# SODIMM.net
KiCad netlist of a schematic drawn in Altium Designer
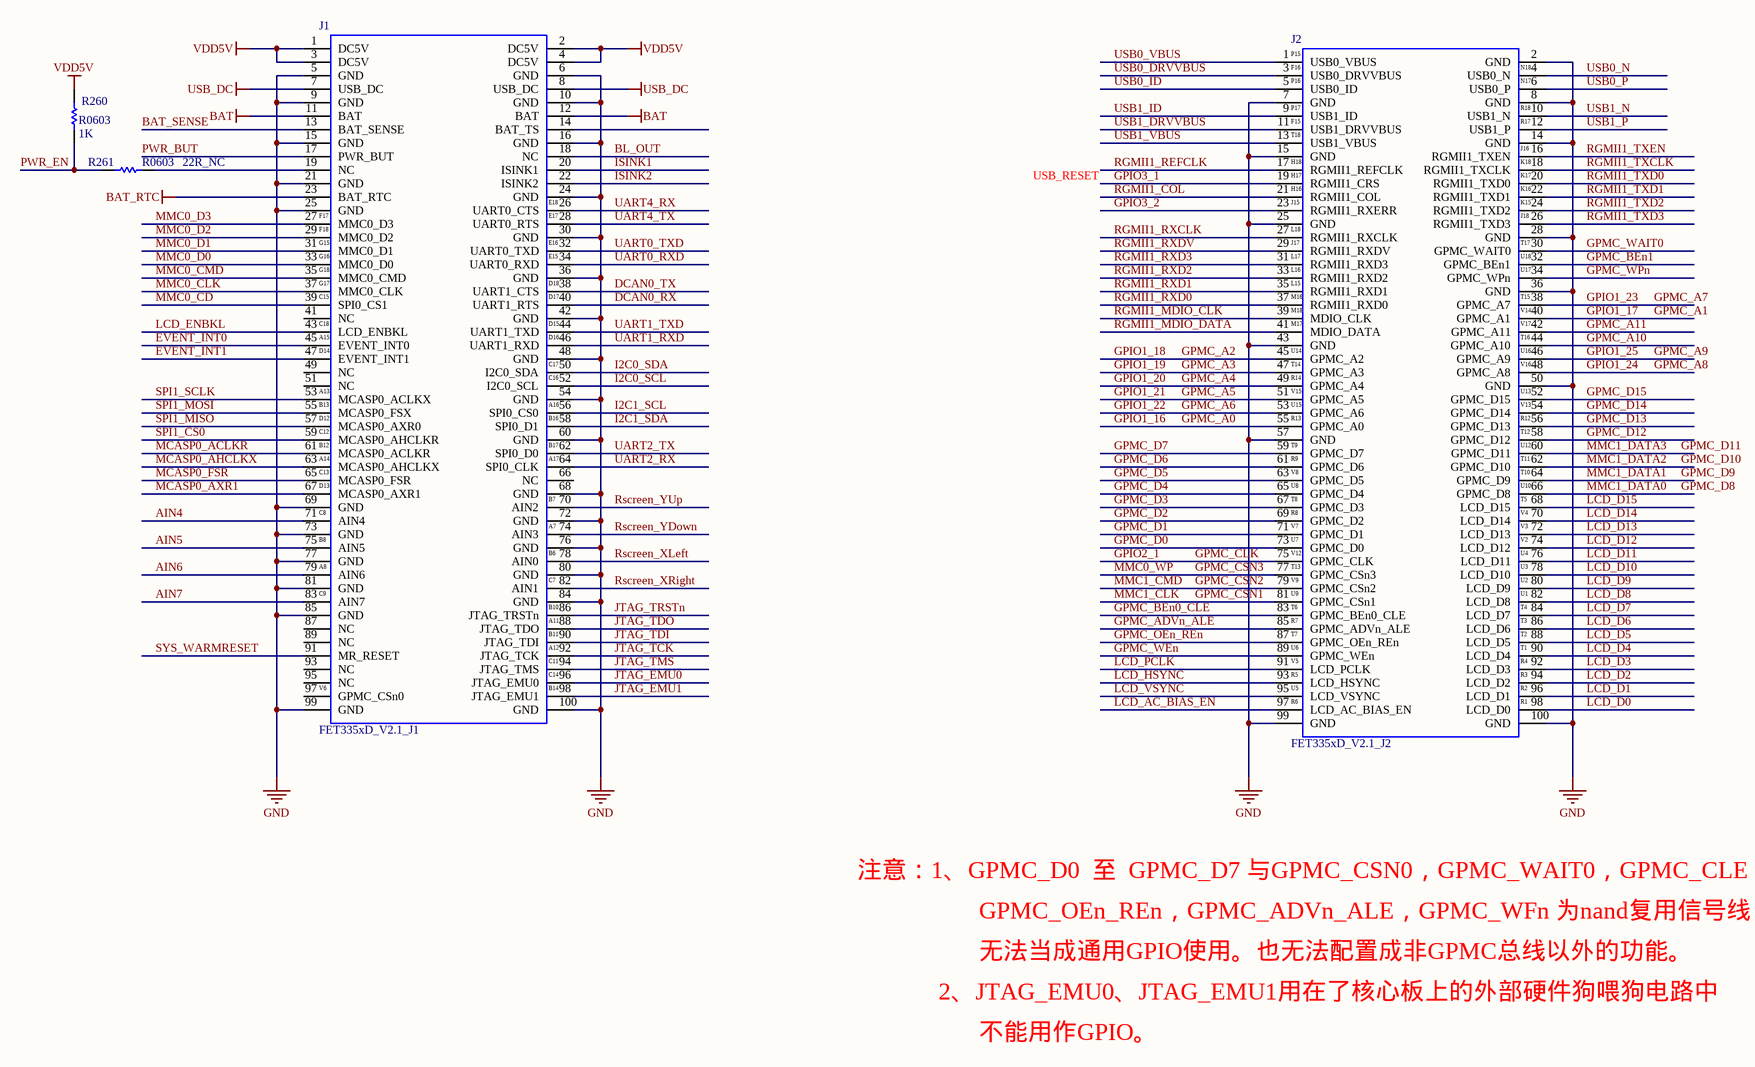
[diagram p0: SODIMM.SchDoc]

(export (version "E")
  (design (tool "Eeschema 10.0.6"))
  (components
    (comp (ref "J1")
      (value "FET335xD_V2.1_J1")
      (footprint "1.27MM SMT CONNECT PIN")
      (libsource (lib "OK335xD") (part "FET335xD_V2.1_J1"))
    )
    (comp (ref "J2")
      (value "FET335xD_V2.1_J2")
      (footprint "1.27MM SMT CONNECT PIN")
      (libsource (lib "OK335xD") (part "FET335xD_V2.1_J2"))
    )
    (comp (ref "R260")
      (value "R0603")
      (footprint "OK335xD_V1.0:R0603_M1608")
      (description "Resistor")
      (fields (field (name "ALTIUM_VALUE") "1K") (field (name "PUBLISHER") "Altium Limited"))
      (libsource (lib "Miscellaneous Devices") (part "Res1"))
    )
    (comp (ref "R261")
      (value "R0603")
      (footprint "OK335xD_V1.0:R0603_M1608")
      (description "Resistor")
      (fields (field (name "ALTIUM_VALUE") "22R_NC") (field (name "PUBLISHER") "Altium Limited"))
      (libsource (lib "Miscellaneous Devices") (part "Res1"))
    )
  )
  (nets
    (net (code "1") (name "/AIN4") (class "Default")
      (node (ref "J1") (pin "71") (pinfunction "AIN4_71") (pintype "passive"))
    )
    (net (code "2") (name "/AIN5") (class "Default")
      (node (ref "J1") (pin "75") (pinfunction "AIN5_75") (pintype "passive"))
    )
    (net (code "3") (name "/AIN6") (class "Default")
      (node (ref "J1") (pin "79") (pinfunction "AIN6_79") (pintype "passive"))
    )
    (net (code "4") (name "/AIN7") (class "Default")
      (node (ref "J1") (pin "83") (pinfunction "AIN7_83") (pintype "passive"))
    )
    (net (code "5") (name "/BAT_SENSE") (class "Default")
      (node (ref "J1") (pin "13") (pinfunction "BAT_SENSE_13") (pintype "passive"))
    )
    (net (code "6") (name "/BL_OUT") (class "Default")
      (node (ref "J1") (pin "18") (pinfunction "NC_18") (pintype "passive"))
    )
    (net (code "7") (name "/DCAN0_RX") (class "Default")
      (node (ref "J1") (pin "40") (pinfunction "UART1_RTS_40") (pintype "passive"))
    )
    (net (code "8") (name "/DCAN0_TX") (class "Default")
      (node (ref "J1") (pin "38") (pinfunction "UART1_CTS_38") (pintype "passive"))
    )
    (net (code "9") (name "/EVENT_INT0") (class "Default")
      (node (ref "J1") (pin "45") (pinfunction "EVENT_INT0_45") (pintype "passive"))
    )
    (net (code "10") (name "/EVENT_INT1") (class "Default")
      (node (ref "J1") (pin "47") (pinfunction "EVENT_INT1_47") (pintype "passive"))
    )
    (net (code "11") (name "/GPIO1_16") (class "Default")
      (node (ref "J2") (pin "55") (pinfunction "GPMC_A0_55") (pintype "passive"))
    )
    (net (code "12") (name "/GPIO1_17") (class "Default")
      (node (ref "J2") (pin "40") (pinfunction "GPMC_A1_40") (pintype "passive"))
    )
    (net (code "13") (name "/GPIO1_18") (class "Default")
      (node (ref "J2") (pin "45") (pinfunction "GPMC_A2_45") (pintype "passive"))
    )
    (net (code "14") (name "/GPIO1_19") (class "Default")
      (node (ref "J2") (pin "47") (pinfunction "GPMC_A3_47") (pintype "passive"))
    )
    (net (code "15") (name "/GPIO1_20") (class "Default")
      (node (ref "J2") (pin "49") (pinfunction "GPMC_A4_49") (pintype "passive"))
    )
    (net (code "16") (name "/GPIO1_21") (class "Default")
      (node (ref "J2") (pin "51") (pinfunction "GPMC_A5_51") (pintype "passive"))
    )
    (net (code "17") (name "/GPIO1_22") (class "Default")
      (node (ref "J2") (pin "53") (pinfunction "GPMC_A6_53") (pintype "passive"))
    )
    (net (code "18") (name "/GPIO1_23") (class "Default")
      (node (ref "J2") (pin "38") (pinfunction "GPMC_A7_38") (pintype "passive"))
    )
    (net (code "19") (name "/GPIO1_24") (class "Default")
      (node (ref "J2") (pin "48") (pinfunction "GPMC_A8_48") (pintype "passive"))
    )
    (net (code "20") (name "/GPIO1_25") (class "Default")
      (node (ref "J2") (pin "46") (pinfunction "GPMC_A9_46") (pintype "passive"))
    )
    (net (code "21") (name "/GPIO2_1") (class "Default")
      (node (ref "J2") (pin "75") (pinfunction "GPMC_CLK_75") (pintype "passive"))
    )
    (net (code "22") (name "/GPIO3_1") (class "Default")
      (node (ref "J2") (pin "19") (pinfunction "RGMII1_CRS_19") (pintype "passive"))
    )
    (net (code "23") (name "/GPIO3_2") (class "Default")
      (node (ref "J2") (pin "23") (pinfunction "RGMII1_RXERR_23") (pintype "passive"))
    )
    (net (code "24") (name "/GPMC_A10") (class "Default")
      (node (ref "J2") (pin "44") (pinfunction "GPMC_A10_44") (pintype "passive"))
    )
    (net (code "25") (name "/GPMC_A11") (class "Default")
      (node (ref "J2") (pin "42") (pinfunction "GPMC_A11_42") (pintype "passive"))
    )
    (net (code "26") (name "/GPMC_ADVn_ALE") (class "Default")
      (node (ref "J2") (pin "85") (pinfunction "GPMC_ADVn_ALE_85") (pintype "passive"))
    )
    (net (code "27") (name "/GPMC_BEn0_CLE") (class "Default")
      (node (ref "J2") (pin "83") (pinfunction "GPMC_BEn0_CLE_83") (pintype "passive"))
    )
    (net (code "28") (name "/GPMC_BEn1") (class "Default")
      (node (ref "J2") (pin "32") (pinfunction "GPMC_BEn1_32") (pintype "passive"))
    )
    (net (code "29") (name "/GPMC_CSN1") (class "Default")
      (node (ref "J2") (pin "81") (pinfunction "GPMC_CSn1_81") (pintype "passive"))
    )
    (net (code "30") (name "/GPMC_CSN2") (class "Default")
      (node (ref "J2") (pin "79") (pinfunction "GPMC_CSn2_79") (pintype "passive"))
    )
    (net (code "31") (name "/GPMC_CSN3") (class "Default")
      (node (ref "J2") (pin "77") (pinfunction "GPMC_CSn3_77") (pintype "passive"))
    )
    (net (code "32") (name "/GPMC_D0") (class "Default")
      (node (ref "J2") (pin "73") (pinfunction "GPMC_D0_73") (pintype "passive"))
    )
    (net (code "33") (name "/GPMC_D1") (class "Default")
      (node (ref "J2") (pin "71") (pinfunction "GPMC_D1_71") (pintype "passive"))
    )
    (net (code "34") (name "/GPMC_D2") (class "Default")
      (node (ref "J2") (pin "69") (pinfunction "GPMC_D2_69") (pintype "passive"))
    )
    (net (code "35") (name "/GPMC_D3") (class "Default")
      (node (ref "J2") (pin "67") (pinfunction "GPMC_D3_67") (pintype "passive"))
    )
    (net (code "36") (name "/GPMC_D4") (class "Default")
      (node (ref "J2") (pin "65") (pinfunction "GPMC_D4_65") (pintype "passive"))
    )
    (net (code "37") (name "/GPMC_D5") (class "Default")
      (node (ref "J2") (pin "63") (pinfunction "GPMC_D5_63") (pintype "passive"))
    )
    (net (code "38") (name "/GPMC_D6") (class "Default")
      (node (ref "J2") (pin "61") (pinfunction "GPMC_D6_61") (pintype "passive"))
    )
    (net (code "39") (name "/GPMC_D7") (class "Default")
      (node (ref "J2") (pin "59") (pinfunction "GPMC_D7_59") (pintype "passive"))
    )
    (net (code "40") (name "/GPMC_D8") (class "Default")
      (node (ref "J2") (pin "66") (pinfunction "GPMC_D8_66") (pintype "passive"))
    )
    (net (code "41") (name "/GPMC_D9") (class "Default")
      (node (ref "J2") (pin "64") (pinfunction "GPMC_D9_64") (pintype "passive"))
    )
    (net (code "42") (name "/GPMC_D10") (class "Default")
      (node (ref "J2") (pin "62") (pinfunction "GPMC_D10_62") (pintype "passive"))
    )
    (net (code "43") (name "/GPMC_D11") (class "Default")
      (node (ref "J2") (pin "60") (pinfunction "GPMC_D11_60") (pintype "passive"))
    )
    (net (code "44") (name "/GPMC_D12") (class "Default")
      (node (ref "J2") (pin "58") (pinfunction "GPMC_D12_58") (pintype "passive"))
    )
    (net (code "45") (name "/GPMC_D13") (class "Default")
      (node (ref "J2") (pin "56") (pinfunction "GPMC_D13_56") (pintype "passive"))
    )
    (net (code "46") (name "/GPMC_D14") (class "Default")
      (node (ref "J2") (pin "54") (pinfunction "GPMC_D14_54") (pintype "passive"))
    )
    (net (code "47") (name "/GPMC_D15") (class "Default")
      (node (ref "J2") (pin "52") (pinfunction "GPMC_D15_52") (pintype "passive"))
    )
    (net (code "48") (name "/GPMC_OEn_REn") (class "Default")
      (node (ref "J2") (pin "87") (pinfunction "GPMC_OEn_REn_87") (pintype "passive"))
    )
    (net (code "49") (name "/GPMC_WAIT0") (class "Default")
      (node (ref "J2") (pin "30") (pinfunction "GPMC_WAIT0_30") (pintype "passive"))
    )
    (net (code "50") (name "/GPMC_WEn") (class "Default")
      (node (ref "J2") (pin "89") (pinfunction "GPMC_WEn_89") (pintype "passive"))
    )
    (net (code "51") (name "/GPMC_WPn") (class "Default")
      (node (ref "J2") (pin "34") (pinfunction "GPMC_WPn_34") (pintype "passive"))
    )
    (net (code "52") (name "/I2C0_SCL") (class "Default")
      (node (ref "J1") (pin "52") (pinfunction "I2C0_SCL_52") (pintype "passive"))
    )
    (net (code "53") (name "/I2C0_SDA") (class "Default")
      (node (ref "J1") (pin "50") (pinfunction "I2C0_SDA_50") (pintype "passive"))
    )
    (net (code "54") (name "/I2C1_SCL") (class "Default")
      (node (ref "J1") (pin "56") (pinfunction "SPI0_CS0_56") (pintype "passive"))
    )
    (net (code "55") (name "/I2C1_SDA") (class "Default")
      (node (ref "J1") (pin "58") (pinfunction "SPI0_D1_58") (pintype "passive"))
    )
    (net (code "56") (name "/ISINK1") (class "Default")
      (node (ref "J1") (pin "20") (pinfunction "ISINK1_20") (pintype "passive"))
    )
    (net (code "57") (name "/ISINK2") (class "Default")
      (node (ref "J1") (pin "22") (pinfunction "ISINK2_22") (pintype "passive"))
    )
    (net (code "58") (name "/JTAG_EMU0") (class "Default")
      (node (ref "J1") (pin "96") (pinfunction "JTAG_EMU0_96") (pintype "passive"))
    )
    (net (code "59") (name "/JTAG_EMU1") (class "Default")
      (node (ref "J1") (pin "98") (pinfunction "JTAG_EMU1_98") (pintype "passive"))
    )
    (net (code "60") (name "/JTAG_TCK") (class "Default")
      (node (ref "J1") (pin "92") (pinfunction "JTAG_TCK_92") (pintype "passive"))
    )
    (net (code "61") (name "/JTAG_TDI") (class "Default")
      (node (ref "J1") (pin "90") (pinfunction "JTAG_TDI_90") (pintype "passive"))
    )
    (net (code "62") (name "/JTAG_TDO") (class "Default")
      (node (ref "J1") (pin "88") (pinfunction "JTAG_TDO_88") (pintype "passive"))
    )
    (net (code "63") (name "/JTAG_TMS") (class "Default")
      (node (ref "J1") (pin "94") (pinfunction "JTAG_TMS_94") (pintype "passive"))
    )
    (net (code "64") (name "/JTAG_TRSTn") (class "Default")
      (node (ref "J1") (pin "86") (pinfunction "JTAG_TRSTn_86") (pintype "passive"))
    )
    (net (code "65") (name "/LCD_AC_BIAS_EN") (class "Default")
      (node (ref "J2") (pin "97") (pinfunction "LCD_AC_BIAS_EN_97") (pintype "passive"))
    )
    (net (code "66") (name "/LCD_D0") (class "Default")
      (node (ref "J2") (pin "98") (pinfunction "LCD_D0_98") (pintype "passive"))
    )
    (net (code "67") (name "/LCD_D1") (class "Default")
      (node (ref "J2") (pin "96") (pinfunction "LCD_D1_96") (pintype "passive"))
    )
    (net (code "68") (name "/LCD_D2") (class "Default")
      (node (ref "J2") (pin "94") (pinfunction "LCD_D2_94") (pintype "passive"))
    )
    (net (code "69") (name "/LCD_D3") (class "Default")
      (node (ref "J2") (pin "92") (pinfunction "LCD_D3_92") (pintype "passive"))
    )
    (net (code "70") (name "/LCD_D4") (class "Default")
      (node (ref "J2") (pin "90") (pinfunction "LCD_D4_90") (pintype "passive"))
    )
    (net (code "71") (name "/LCD_D5") (class "Default")
      (node (ref "J2") (pin "88") (pinfunction "LCD_D5_88") (pintype "passive"))
    )
    (net (code "72") (name "/LCD_D6") (class "Default")
      (node (ref "J2") (pin "86") (pinfunction "LCD_D6_86") (pintype "passive"))
    )
    (net (code "73") (name "/LCD_D7") (class "Default")
      (node (ref "J2") (pin "84") (pinfunction "LCD_D7_84") (pintype "passive"))
    )
    (net (code "74") (name "/LCD_D8") (class "Default")
      (node (ref "J2") (pin "82") (pinfunction "LCD_D8_82") (pintype "passive"))
    )
    (net (code "75") (name "/LCD_D9") (class "Default")
      (node (ref "J2") (pin "80") (pinfunction "LCD_D9_80") (pintype "passive"))
    )
    (net (code "76") (name "/LCD_D10") (class "Default")
      (node (ref "J2") (pin "78") (pinfunction "LCD_D10_78") (pintype "passive"))
    )
    (net (code "77") (name "/LCD_D11") (class "Default")
      (node (ref "J2") (pin "76") (pinfunction "LCD_D11_76") (pintype "passive"))
    )
    (net (code "78") (name "/LCD_D12") (class "Default")
      (node (ref "J2") (pin "74") (pinfunction "LCD_D12_74") (pintype "passive"))
    )
    (net (code "79") (name "/LCD_D13") (class "Default")
      (node (ref "J2") (pin "72") (pinfunction "LCD_D13_72") (pintype "passive"))
    )
    (net (code "80") (name "/LCD_D14") (class "Default")
      (node (ref "J2") (pin "70") (pinfunction "LCD_D14_70") (pintype "passive"))
    )
    (net (code "81") (name "/LCD_D15") (class "Default")
      (node (ref "J2") (pin "68") (pinfunction "LCD_D15_68") (pintype "passive"))
    )
    (net (code "82") (name "/LCD_ENBKL") (class "Default")
      (node (ref "J1") (pin "43") (pinfunction "LCD_ENBKL_43") (pintype "passive"))
    )
    (net (code "83") (name "/LCD_HSYNC") (class "Default")
      (node (ref "J2") (pin "93") (pinfunction "LCD_HSYNC_93") (pintype "passive"))
    )
    (net (code "84") (name "/LCD_PCLK") (class "Default")
      (node (ref "J2") (pin "91") (pinfunction "LCD_PCLK_91") (pintype "passive"))
    )
    (net (code "85") (name "/LCD_VSYNC") (class "Default")
      (node (ref "J2") (pin "95") (pinfunction "LCD_VSYNC_95") (pintype "passive"))
    )
    (net (code "86") (name "/MCASP0_ACLKR") (class "Default")
      (node (ref "J1") (pin "61") (pinfunction "MCASP0_ACLKR_61") (pintype "passive"))
    )
    (net (code "87") (name "/MCASP0_AHCLKX") (class "Default")
      (node (ref "J1") (pin "63") (pinfunction "MCASP0_AHCLKX_63") (pintype "passive"))
    )
    (net (code "88") (name "/MCASP0_AXR1") (class "Default")
      (node (ref "J1") (pin "67") (pinfunction "MCASP0_AXR1_67") (pintype "passive"))
    )
    (net (code "89") (name "/MCASP0_FSR") (class "Default")
      (node (ref "J1") (pin "65") (pinfunction "MCASP0_FSR_65") (pintype "passive"))
    )
    (net (code "90") (name "/MMC0_CD") (class "Default")
      (node (ref "J1") (pin "39") (pinfunction "SPI0_CS1_39") (pintype "passive"))
    )
    (net (code "91") (name "/MMC0_CLK") (class "Default")
      (node (ref "J1") (pin "37") (pinfunction "MMC0_CLK_37") (pintype "passive"))
    )
    (net (code "92") (name "/MMC0_CMD") (class "Default")
      (node (ref "J1") (pin "35") (pinfunction "MMC0_CMD_35") (pintype "passive"))
    )
    (net (code "93") (name "/MMC0_D0") (class "Default")
      (node (ref "J1") (pin "33") (pinfunction "MMC0_D0_33") (pintype "passive"))
    )
    (net (code "94") (name "/MMC0_D1") (class "Default")
      (node (ref "J1") (pin "31") (pinfunction "MMC0_D1_31") (pintype "passive"))
    )
    (net (code "95") (name "/MMC0_D2") (class "Default")
      (node (ref "J1") (pin "29") (pinfunction "MMC0_D2_29") (pintype "passive"))
    )
    (net (code "96") (name "/MMC0_D3") (class "Default")
      (node (ref "J1") (pin "27") (pinfunction "MMC0_D3_27") (pintype "passive"))
    )
    (net (code "97") (name "/PWR_BUT") (class "Default")
      (node (ref "J1") (pin "17") (pinfunction "PWR_BUT_17") (pintype "passive"))
    )
    (net (code "98") (name "/PWR_EN") (class "Default")
      (node (ref "R260") (pin "2") (pinfunction "2_2") (pintype "passive"))
      (node (ref "R261") (pin "1") (pinfunction "1_1") (pintype "passive"))
    )
    (net (code "99") (name "/RGMII1_COL") (class "Default")
      (node (ref "J2") (pin "21") (pinfunction "RGMII1_COL_21") (pintype "passive"))
    )
    (net (code "100") (name "/RGMII1_MDIO_CLK") (class "Default")
      (node (ref "J2") (pin "39") (pinfunction "MDIO_CLK_39") (pintype "passive"))
    )
    (net (code "101") (name "/RGMII1_MDIO_DATA") (class "Default")
      (node (ref "J2") (pin "41") (pinfunction "MDIO_DATA_41") (pintype "passive"))
    )
    (net (code "102") (name "/RGMII1_REFCLK") (class "Default")
      (node (ref "J2") (pin "17") (pinfunction "RGMII1_REFCLK_17") (pintype "passive"))
    )
    (net (code "103") (name "/RGMII1_RXCLK") (class "Default")
      (node (ref "J2") (pin "27") (pinfunction "RGMII1_RXCLK_27") (pintype "passive"))
    )
    (net (code "104") (name "/RGMII1_RXD0") (class "Default")
      (node (ref "J2") (pin "37") (pinfunction "RGMII1_RXD0_37") (pintype "passive"))
    )
    (net (code "105") (name "/RGMII1_RXD1") (class "Default")
      (node (ref "J2") (pin "35") (pinfunction "RGMII1_RXD1_35") (pintype "passive"))
    )
    (net (code "106") (name "/RGMII1_RXD2") (class "Default")
      (node (ref "J2") (pin "33") (pinfunction "RGMII1_RXD2_33") (pintype "passive"))
    )
    (net (code "107") (name "/RGMII1_RXD3") (class "Default")
      (node (ref "J2") (pin "31") (pinfunction "RGMII1_RXD3_31") (pintype "passive"))
    )
    (net (code "108") (name "/RGMII1_RXDV") (class "Default")
      (node (ref "J2") (pin "29") (pinfunction "RGMII1_RXDV_29") (pintype "passive"))
    )
    (net (code "109") (name "/RGMII1_TXCLK") (class "Default")
      (node (ref "J2") (pin "18") (pinfunction "RGMII1_TXCLK_18") (pintype "passive"))
    )
    (net (code "110") (name "/RGMII1_TXD0") (class "Default")
      (node (ref "J2") (pin "20") (pinfunction "RGMII1_TXD0_20") (pintype "passive"))
    )
    (net (code "111") (name "/RGMII1_TXD1") (class "Default")
      (node (ref "J2") (pin "22") (pinfunction "RGMII1_TXD1_22") (pintype "passive"))
    )
    (net (code "112") (name "/RGMII1_TXD2") (class "Default")
      (node (ref "J2") (pin "24") (pinfunction "RGMII1_TXD2_24") (pintype "passive"))
    )
    (net (code "113") (name "/RGMII1_TXD3") (class "Default")
      (node (ref "J2") (pin "26") (pinfunction "RGMII1_TXD3_26") (pintype "passive"))
    )
    (net (code "114") (name "/RGMII1_TXEN") (class "Default")
      (node (ref "J2") (pin "16") (pinfunction "RGMII1_TXEN_16") (pintype "passive"))
    )
    (net (code "115") (name "/Rscreen_XLeft") (class "Default")
      (node (ref "J1") (pin "78") (pinfunction "AIN0_78") (pintype "passive"))
    )
    (net (code "116") (name "/Rscreen_XRight") (class "Default")
      (node (ref "J1") (pin "82") (pinfunction "AIN1_82") (pintype "passive"))
    )
    (net (code "117") (name "/Rscreen_YDown") (class "Default")
      (node (ref "J1") (pin "74") (pinfunction "AIN3_74") (pintype "passive"))
    )
    (net (code "118") (name "/Rscreen_YUp") (class "Default")
      (node (ref "J1") (pin "70") (pinfunction "AIN2_70") (pintype "passive"))
    )
    (net (code "119") (name "/SPI1_CS0") (class "Default")
      (node (ref "J1") (pin "59") (pinfunction "MCASP0_AHCLKR_59") (pintype "passive"))
    )
    (net (code "120") (name "/SPI1_MISO") (class "Default")
      (node (ref "J1") (pin "57") (pinfunction "MCASP0_AXR0_57") (pintype "passive"))
    )
    (net (code "121") (name "/SPI1_MOSI") (class "Default")
      (node (ref "J1") (pin "55") (pinfunction "MCASP0_FSX_55") (pintype "passive"))
    )
    (net (code "122") (name "/SPI1_SCLK") (class "Default")
      (node (ref "J1") (pin "53") (pinfunction "MCASP0_ACLKX_53") (pintype "passive"))
    )
    (net (code "123") (name "/SYS_WARMRESET") (class "Default")
      (node (ref "J1") (pin "91") (pinfunction "MR_RESET_91") (pintype "passive"))
    )
    (net (code "124") (name "/UART0_RXD") (class "Default")
      (node (ref "J1") (pin "34") (pinfunction "UART0_RXD_34") (pintype "passive"))
    )
    (net (code "125") (name "/UART0_TXD") (class "Default")
      (node (ref "J1") (pin "32") (pinfunction "UART0_TXD_32") (pintype "passive"))
    )
    (net (code "126") (name "/UART1_RXD") (class "Default")
      (node (ref "J1") (pin "46") (pinfunction "UART1_RXD_46") (pintype "passive"))
    )
    (net (code "127") (name "/UART1_TXD") (class "Default")
      (node (ref "J1") (pin "44") (pinfunction "UART1_TXD_44") (pintype "passive"))
    )
    (net (code "128") (name "/UART2_RX") (class "Default")
      (node (ref "J1") (pin "64") (pinfunction "SPI0_CLK_64") (pintype "passive"))
    )
    (net (code "129") (name "/UART2_TX") (class "Default")
      (node (ref "J1") (pin "62") (pinfunction "SPI0_D0_62") (pintype "passive"))
    )
    (net (code "130") (name "/UART4_RX") (class "Default")
      (node (ref "J1") (pin "26") (pinfunction "UART0_CTS_26") (pintype "passive"))
    )
    (net (code "131") (name "/UART4_TX") (class "Default")
      (node (ref "J1") (pin "28") (pinfunction "UART0_RTS_28") (pintype "passive"))
    )
    (net (code "132") (name "/USB0_DRVVBUS") (class "Default")
      (node (ref "J2") (pin "3") (pinfunction "USB0_DRVVBUS_3") (pintype "passive"))
    )
    (net (code "133") (name "/USB0_ID") (class "Default")
      (node (ref "J2") (pin "5") (pinfunction "USB0_ID_5") (pintype "passive"))
    )
    (net (code "134") (name "/USB0_N") (class "Default")
      (node (ref "J2") (pin "4") (pinfunction "USB0_N_4") (pintype "passive"))
    )
    (net (code "135") (name "/USB0_P") (class "Default")
      (node (ref "J2") (pin "6") (pinfunction "USB0_P_6") (pintype "passive"))
    )
    (net (code "136") (name "/USB0_VBUS") (class "Default")
      (node (ref "J2") (pin "1") (pinfunction "USB0_VBUS_1") (pintype "passive"))
    )
    (net (code "137") (name "/USB1_DRVVBUS") (class "Default")
      (node (ref "J2") (pin "11") (pinfunction "USB1_DRVVBUS_11") (pintype "passive"))
    )
    (net (code "138") (name "/USB1_ID") (class "Default")
      (node (ref "J2") (pin "9") (pinfunction "USB1_ID_9") (pintype "passive"))
    )
    (net (code "139") (name "/USB1_N") (class "Default")
      (node (ref "J2") (pin "10") (pinfunction "USB1_N_10") (pintype "passive"))
    )
    (net (code "140") (name "/USB1_P") (class "Default")
      (node (ref "J2") (pin "12") (pinfunction "USB1_P_12") (pintype "passive"))
    )
    (net (code "141") (name "/USB1_VBUS") (class "Default")
      (node (ref "J2") (pin "13") (pinfunction "USB1_VBUS_13") (pintype "passive"))
    )
    (net (code "142") (name "BAT") (class "Default")
      (node (ref "J1") (pin "11") (pinfunction "BAT_11") (pintype "passive"))
      (node (ref "J1") (pin "12") (pinfunction "BAT_12") (pintype "passive"))
    )
    (net (code "143") (name "BAT_RTC") (class "Default")
      (node (ref "J1") (pin "23") (pinfunction "BAT_RTC_23") (pintype "passive"))
    )
    (net (code "144") (name "GND") (class "Default")
      (node (ref "J1") (pin "10") (pinfunction "GND_10") (pintype "passive"))
      (node (ref "J1") (pin "100") (pinfunction "GND_100") (pintype "passive"))
      (node (ref "J1") (pin "15") (pinfunction "GND_15") (pintype "passive"))
      (node (ref "J1") (pin "16") (pinfunction "GND_16") (pintype "passive"))
      (node (ref "J1") (pin "21") (pinfunction "GND_21") (pintype "passive"))
      (node (ref "J1") (pin "24") (pinfunction "GND_24") (pintype "passive"))
      (node (ref "J1") (pin "25") (pinfunction "GND_25") (pintype "passive"))
      (node (ref "J1") (pin "30") (pinfunction "GND_30") (pintype "passive"))
      (node (ref "J1") (pin "36") (pinfunction "GND_36") (pintype "passive"))
      (node (ref "J1") (pin "42") (pinfunction "GND_42") (pintype "passive"))
      (node (ref "J1") (pin "48") (pinfunction "GND_48") (pintype "passive"))
      (node (ref "J1") (pin "5") (pinfunction "GND_5") (pintype "passive"))
      (node (ref "J1") (pin "54") (pinfunction "GND_54") (pintype "passive"))
      (node (ref "J1") (pin "6") (pinfunction "GND_6") (pintype "passive"))
      (node (ref "J1") (pin "60") (pinfunction "GND_60") (pintype "passive"))
      (node (ref "J1") (pin "68") (pinfunction "GND_68") (pintype "passive"))
      (node (ref "J1") (pin "69") (pinfunction "GND_69") (pintype "passive"))
      (node (ref "J1") (pin "72") (pinfunction "GND_72") (pintype "passive"))
      (node (ref "J1") (pin "73") (pinfunction "GND_73") (pintype "passive"))
      (node (ref "J1") (pin "76") (pinfunction "GND_76") (pintype "passive"))
      (node (ref "J1") (pin "77") (pinfunction "GND_77") (pintype "passive"))
      (node (ref "J1") (pin "80") (pinfunction "GND_80") (pintype "passive"))
      (node (ref "J1") (pin "81") (pinfunction "GND_81") (pintype "passive"))
      (node (ref "J1") (pin "84") (pinfunction "GND_84") (pintype "passive"))
      (node (ref "J1") (pin "85") (pinfunction "GND_85") (pintype "passive"))
      (node (ref "J1") (pin "9") (pinfunction "GND_9") (pintype "passive"))
      (node (ref "J1") (pin "99") (pinfunction "GND_99") (pintype "passive"))
      (node (ref "J2") (pin "100") (pinfunction "GND_100") (pintype "passive"))
      (node (ref "J2") (pin "14") (pinfunction "GND_14") (pintype "passive"))
      (node (ref "J2") (pin "15") (pinfunction "GND_15") (pintype "passive"))
      (node (ref "J2") (pin "2") (pinfunction "GND_2") (pintype "passive"))
      (node (ref "J2") (pin "25") (pinfunction "GND_25") (pintype "passive"))
      (node (ref "J2") (pin "28") (pinfunction "GND_28") (pintype "passive"))
      (node (ref "J2") (pin "36") (pinfunction "GND_36") (pintype "passive"))
      (node (ref "J2") (pin "43") (pinfunction "GND_43") (pintype "passive"))
      (node (ref "J2") (pin "50") (pinfunction "GND_50") (pintype "passive"))
      (node (ref "J2") (pin "57") (pinfunction "GND_57") (pintype "passive"))
      (node (ref "J2") (pin "7") (pinfunction "GND_7") (pintype "passive"))
      (node (ref "J2") (pin "8") (pinfunction "GND_8") (pintype "passive"))
      (node (ref "J2") (pin "99") (pinfunction "GND_99") (pintype "passive"))
    )
    (net (code "145") (name "Net-(J1-NC-Pad19)") (class "Default")
      (node (ref "J1") (pin "19") (pinfunction "NC_19") (pintype "passive"))
      (node (ref "R261") (pin "2") (pinfunction "2_2") (pintype "passive"))
    )
    (net (code "146") (name "USB_DC") (class "Default")
      (node (ref "J1") (pin "7") (pinfunction "USB_DC_7") (pintype "passive"))
      (node (ref "J1") (pin "8") (pinfunction "USB_DC_8") (pintype "passive"))
    )
    (net (code "147") (name "VDD5V") (class "Default")
      (node (ref "J1") (pin "1") (pinfunction "DC5V_1") (pintype "passive"))
      (node (ref "J1") (pin "2") (pinfunction "DC5V_2") (pintype "passive"))
      (node (ref "J1") (pin "3") (pinfunction "DC5V_3") (pintype "passive"))
      (node (ref "J1") (pin "4") (pinfunction "DC5V_4") (pintype "passive"))
      (node (ref "R260") (pin "1") (pinfunction "1_1") (pintype "passive"))
    )
    (net (code "148") (name "unconnected-(J1-BAT_TS-Pad14)") (class "Default")
      (node (ref "J1") (pin "14") (pinfunction "BAT_TS_14") (pintype "passive"))
    )
    (net (code "149") (name "unconnected-(J1-GPMC_CSn0-Pad97)") (class "Default")
      (node (ref "J1") (pin "97") (pinfunction "GPMC_CSn0_97") (pintype "passive"))
    )
    (net (code "150") (name "unconnected-(J1-NC-Pad41)") (class "Default")
      (node (ref "J1") (pin "41") (pinfunction "NC_41") (pintype "passive"))
    )
    (net (code "151") (name "unconnected-(J1-NC-Pad49)") (class "Default")
      (node (ref "J1") (pin "49") (pinfunction "NC_49") (pintype "passive"))
    )
    (net (code "152") (name "unconnected-(J1-NC-Pad51)") (class "Default")
      (node (ref "J1") (pin "51") (pinfunction "NC_51") (pintype "passive"))
    )
    (net (code "153") (name "unconnected-(J1-NC-Pad66)") (class "Default")
      (node (ref "J1") (pin "66") (pinfunction "NC_66") (pintype "passive"))
    )
    (net (code "154") (name "unconnected-(J1-NC-Pad87)") (class "Default")
      (node (ref "J1") (pin "87") (pinfunction "NC_87") (pintype "passive"))
    )
    (net (code "155") (name "unconnected-(J1-NC-Pad89)") (class "Default")
      (node (ref "J1") (pin "89") (pinfunction "NC_89") (pintype "passive"))
    )
    (net (code "156") (name "unconnected-(J1-NC-Pad93)") (class "Default")
      (node (ref "J1") (pin "93") (pinfunction "NC_93") (pintype "passive"))
    )
    (net (code "157") (name "unconnected-(J1-NC-Pad95)") (class "Default")
      (node (ref "J1") (pin "95") (pinfunction "NC_95") (pintype "passive"))
    )
  )
)
